# SCH_LED_drill_2025-12-10.net
KiCad netlist of a schematic drawn in EasyEDA
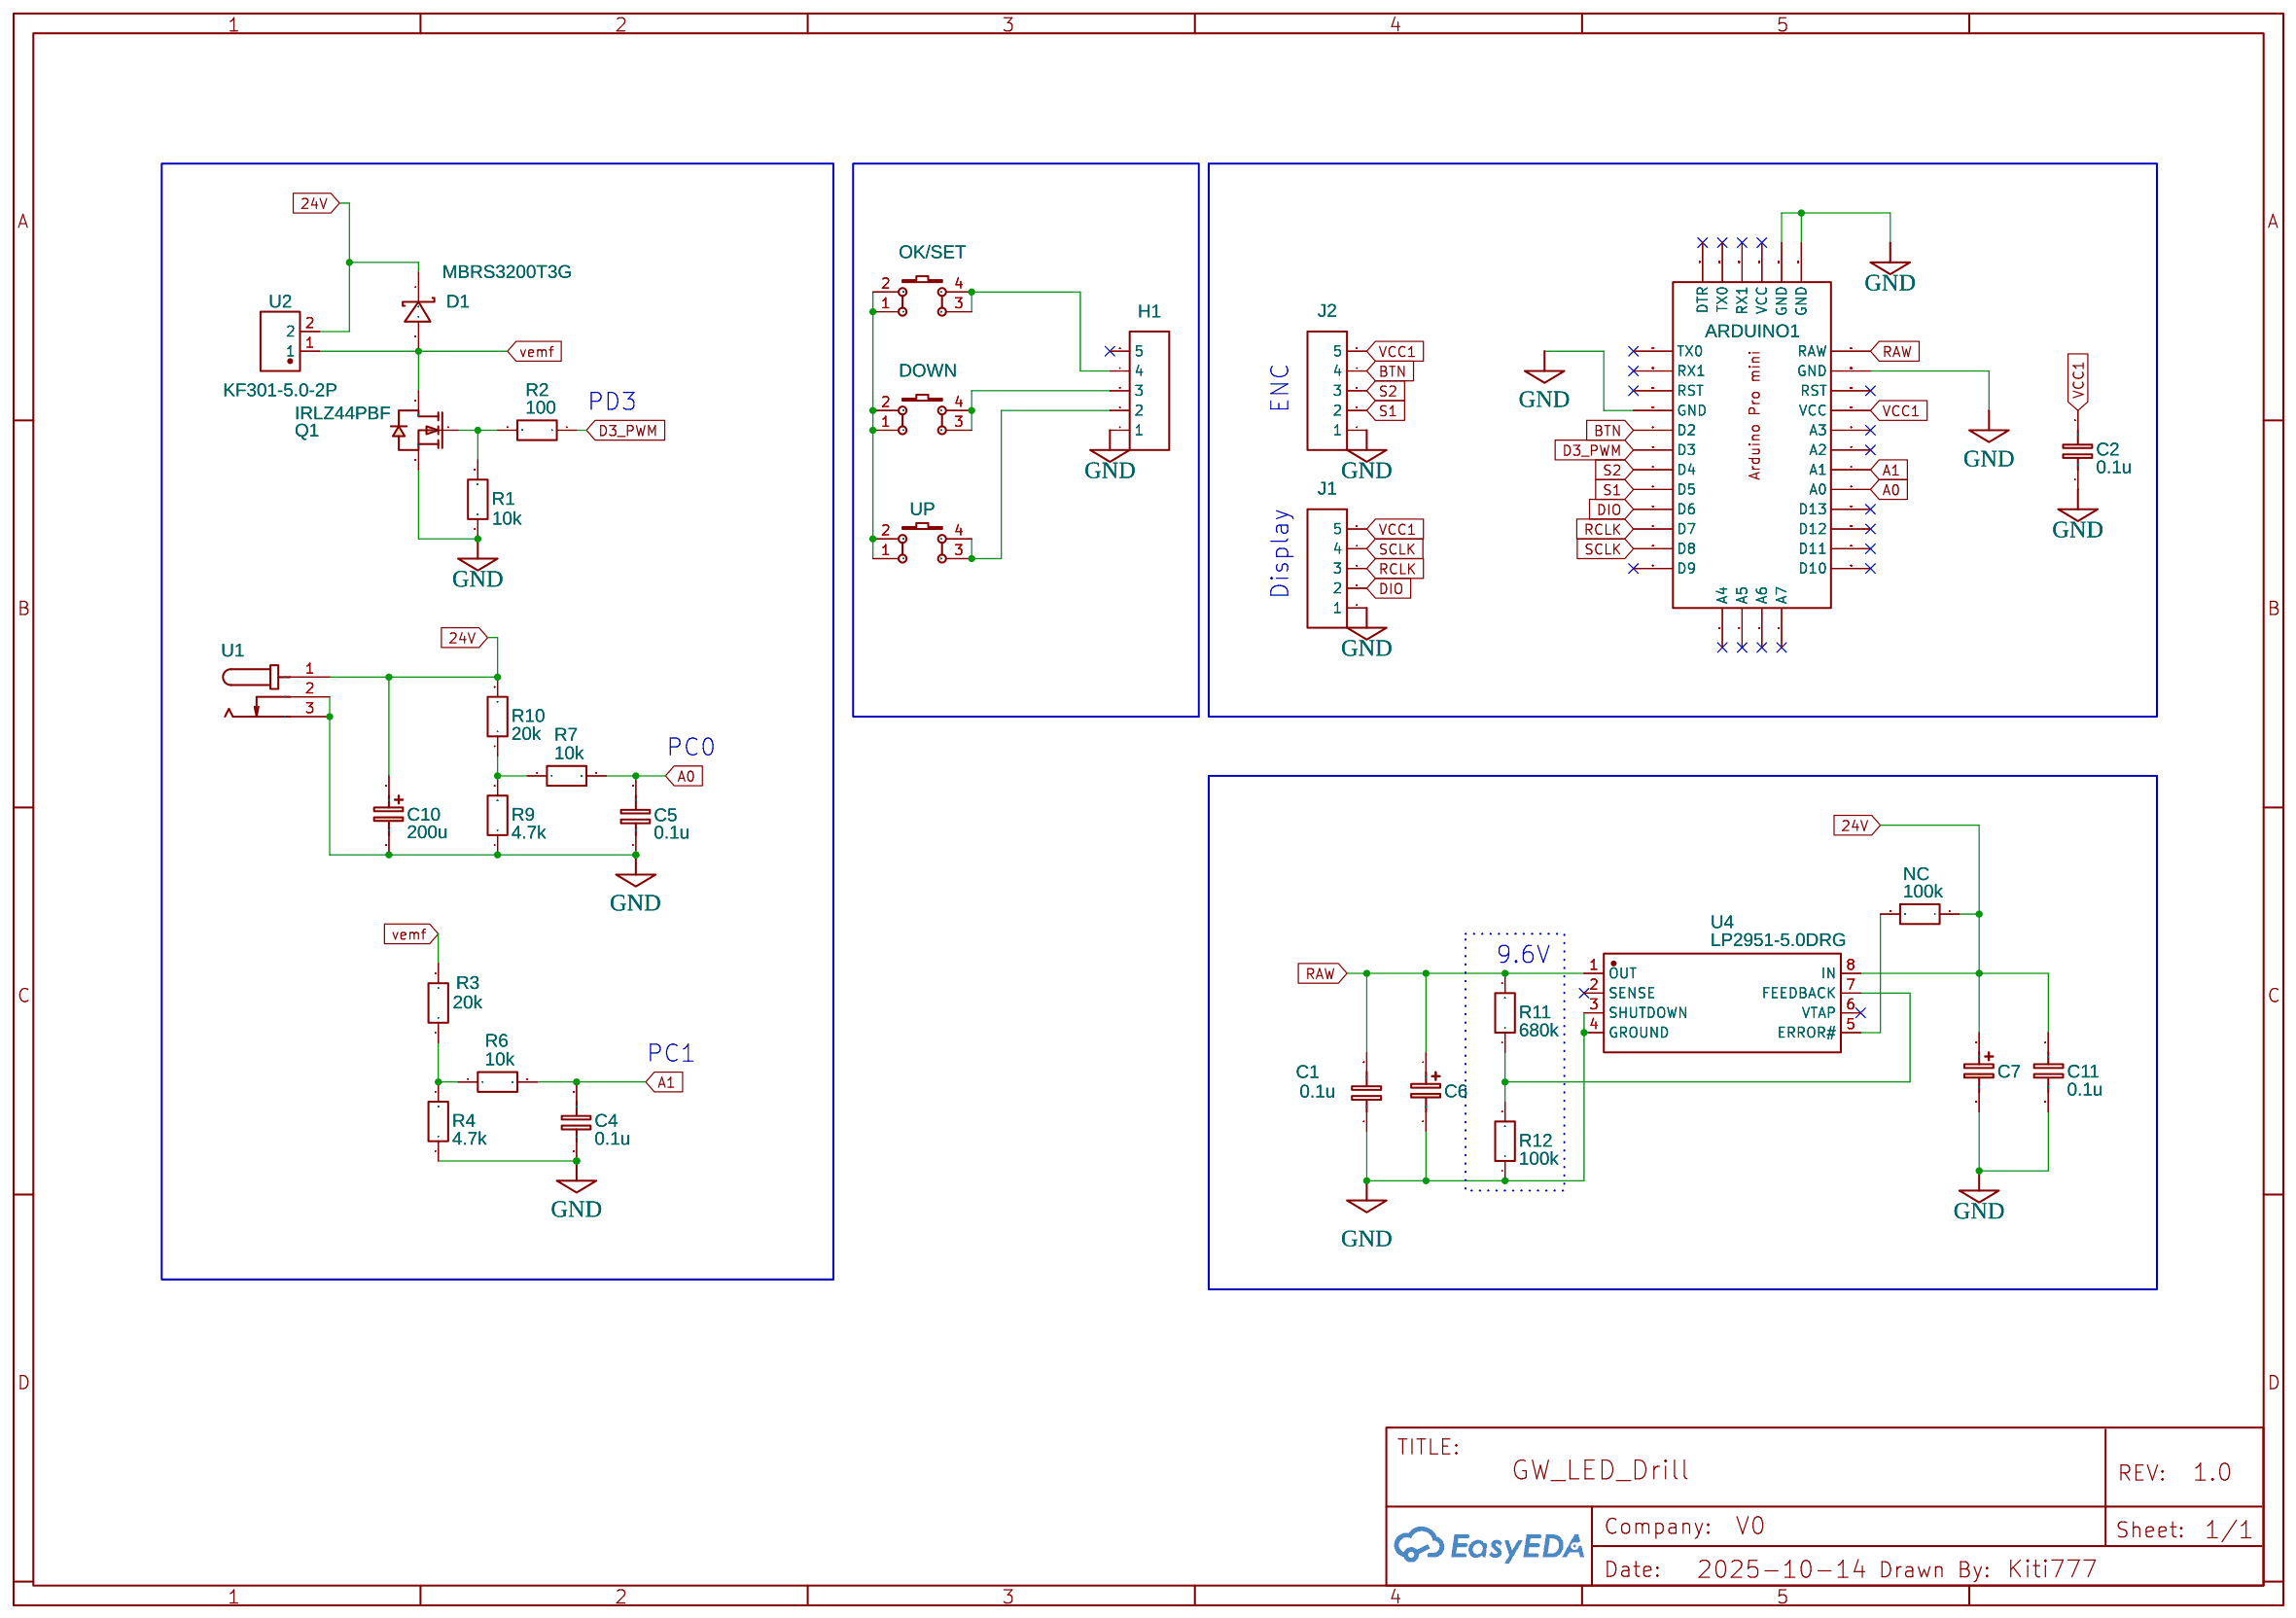
[diagram p0: schematic sheet]

(export (version "E")
  (design (tool "Eeschema 10.0.6"))
  (components
    (comp (ref "ARDUINO1") (value "ARDUINO PRO MINI") (libsource (lib "") (part "ARDUINO PRO MINI")))
    (comp (ref "C1") (value "0.1u") (libsource (lib "") (part "C_1206_EU_2")))
    (comp (ref "C2") (value "0.1u") (libsource (lib "") (part "C_0805_EU_1")))
    (comp (ref "C4") (value "0.1u") (libsource (lib "") (part "C_0805_EU")))
    (comp (ref "C5") (value "0.1u") (libsource (lib "") (part "C_1206_EU_1")))
    (comp (ref "C6")
      (value "TANTALUM SMT CAPACITOR 330UF C")
      (fields (field (name "Manufacturer Part") "Tantalum SMT Capacitor 330uF C"))
      (libsource (lib "") (part "TANTALUM SMT CAPACITOR 330UF C"))
    )
    (comp (ref "C7")
      (value "TANTALUM SMT CAPACITOR 330UF C")
      (fields (field (name "Manufacturer Part") "Tantalum SMT Capacitor 330uF C"))
      (libsource (lib "") (part "TANTALUM SMT CAPACITOR 330UF C"))
    )
    (comp (ref "C10") (value "200u") (libsource (lib "") (part "CE_SMD_D8.0×H10.5_EU")))
    (comp (ref "C11") (value "0.1u") (libsource (lib "") (part "C_1206_EU")))
    (comp (ref "D1")
      (value "MBRS3200T3G")
      (fields (field (name "Manufacturer") "onsemi(安森美)"))
      (libsource (lib "") (part "MBRS3200T3G"))
    )
    (comp (ref "DOWN")
      (value "K4-6×6_TH")
      (fields (field (name "Manufacturer Part") "K2-1102DP-E4SW-04") (field (name "Manufacturer") "韩国韩荣"))
      (libsource (lib "") (part "K4-6×6_TH"))
    )
    (comp (ref "H1") (value "HDR-F-2.54_1x5") (libsource (lib "") (part "HDR-F-2.54_1x5")))
    (comp (ref "J1") (value "HDR-M-2.54_1x5") (libsource (lib "") (part "HDR-M-2.54_1x5")))
    (comp (ref "J2") (value "HDR-M-2.54_1x5") (libsource (lib "") (part "HDR-M-2.54_1x5")))
    (comp (ref "NC") (value "100k") (libsource (lib "") (part "R_0805_EU_1")))
    (comp (ref "OK/SET")
      (value "K4-6×6_TH")
      (fields (field (name "Manufacturer Part") "K2-1102DP-E4SW-04") (field (name "Manufacturer") "韩国韩荣"))
      (libsource (lib "") (part "K4-6×6_TH_2"))
    )
    (comp (ref "Q1")
      (value "IRLZ44PBF")
      (fields (field (name "Manufacturer Part") "IRLZ44PBF-VB") (field (name "Manufacturer") "VBsemi(微碧半导体)"))
      (libsource (lib "") (part "IRLZ44PBF"))
    )
    (comp (ref "R1") (value "10k") (libsource (lib "") (part "R_1206_EU_1")))
    (comp (ref "R2") (value "100") (libsource (lib "") (part "R_1206_EU_2")))
    (comp (ref "R3") (value "20k") (libsource (lib "") (part "R_1206_EU_1")))
    (comp (ref "R4") (value "4.7k") (libsource (lib "") (part "R_1206_EU_1")))
    (comp (ref "R6") (value "10k") (libsource (lib "") (part "R_1206_EU")))
    (comp (ref "R7") (value "10k") (libsource (lib "") (part "R_1206_EU")))
    (comp (ref "R9") (value "4.7k") (libsource (lib "") (part "R_1206_EU_1")))
    (comp (ref "R10") (value "20k") (libsource (lib "") (part "R_1206_EU_1")))
    (comp (ref "R11") (value "680k") (libsource (lib "") (part "R_0805_EU")))
    (comp (ref "R12") (value "100k") (libsource (lib "") (part "R_0805_EU")))
    (comp (ref "U1")
      (value "ZX-DC-WC26.4")
      (fields (field (name "Manufacturer") "Megastar(兆星)"))
      (libsource (lib "") (part "ZX-DC-WC26.4"))
    )
    (comp (ref "U2")
      (value "KF301-5.0-2P")
      (fields (field (name "Manufacturer") "KEFA(科发)"))
      (libsource (lib "") (part "KF301-5.0-2P"))
    )
    (comp (ref "U4")
      (value "LP2951-5.0DRG")
      (fields (field (name "Manufacturer") "HGC(深圳汉芯)"))
      (libsource (lib "") (part "LP2951-5.0DRG"))
    )
    (comp (ref "UP")
      (value "K4-6×6_TH")
      (fields (field (name "Manufacturer Part") "K2-1102DP-E4SW-04") (field (name "Manufacturer") "韩国韩荣"))
      (libsource (lib "") (part "K4-6×6_TH_1"))
    )
  )
  (nets
    (net (code "1") (name "24V") (class "Default")
      (node (ref "C10") (pin "1") (pinfunction "1_1") (pintype "unspecified"))
      (node (ref "C11") (pin "1") (pinfunction "1_1") (pintype "unspecified"))
      (node (ref "C7") (pin "1") (pinfunction "1_1") (pintype "unspecified"))
      (node (ref "D1") (pin "1") (pinfunction "C_1") (pintype "unspecified"))
      (node (ref "NC") (pin "1") (pinfunction "1_1") (pintype "unspecified"))
      (node (ref "R10") (pin "2") (pinfunction "2_2") (pintype "unspecified"))
      (node (ref "U1") (pin "1") (pinfunction "1_1") (pintype "unspecified"))
      (node (ref "U2") (pin "2") (pinfunction "2_2") (pintype "unspecified"))
      (node (ref "U4") (pin "8") (pinfunction "IN_8") (pintype "unspecified"))
    )
    (net (code "2") (name "A0") (class "Default")
      (node (ref "ARDUINO1") (pin "A0") (pinfunction "A0_A0") (pintype "bidirectional"))
      (node (ref "C5") (pin "2") (pinfunction "2_2") (pintype "unspecified"))
      (node (ref "R7") (pin "2") (pinfunction "2_2") (pintype "unspecified"))
    )
    (net (code "3") (name "A1") (class "Default")
      (node (ref "ARDUINO1") (pin "A1") (pinfunction "A1_A1") (pintype "bidirectional"))
      (node (ref "C4") (pin "2") (pinfunction "2_2") (pintype "unspecified"))
      (node (ref "R6") (pin "2") (pinfunction "2_2") (pintype "unspecified"))
    )
    (net (code "4") (name "BTN") (class "Default")
      (node (ref "ARDUINO1") (pin "D2") (pinfunction "D2_D2") (pintype "bidirectional"))
      (node (ref "J2") (pin "4") (pinfunction "4_4") (pintype "unspecified"))
    )
    (net (code "5") (name "D3_PWM") (class "Default")
      (node (ref "ARDUINO1") (pin "D3") (pinfunction "D3_D3") (pintype "bidirectional"))
      (node (ref "R2") (pin "1") (pinfunction "1_1") (pintype "unspecified"))
    )
    (net (code "6") (name "DIO") (class "Default")
      (node (ref "ARDUINO1") (pin "D6") (pinfunction "D6_D6") (pintype "bidirectional"))
      (node (ref "J1") (pin "2") (pinfunction "2_2") (pintype "unspecified"))
    )
    (net (code "7") (name "GND") (class "Default")
      (node (ref "ARDUINO1") (pin "GND@0") (pinfunction "GND_GND@0") (pintype "bidirectional"))
      (node (ref "ARDUINO1") (pin "GND@1") (pinfunction "GND_GND@1") (pintype "bidirectional"))
      (node (ref "ARDUINO1") (pin "GND@2") (pinfunction "GND_GND@2") (pintype "bidirectional"))
      (node (ref "ARDUINO1") (pin "GND@3") (pinfunction "GND_GND@3") (pintype "bidirectional"))
      (node (ref "C1") (pin "1") (pinfunction "1_1") (pintype "unspecified"))
      (node (ref "C10") (pin "2") (pinfunction "2_2") (pintype "unspecified"))
      (node (ref "C11") (pin "2") (pinfunction "2_2") (pintype "unspecified"))
      (node (ref "C2") (pin "1") (pinfunction "1_1") (pintype "unspecified"))
      (node (ref "C4") (pin "1") (pinfunction "1_1") (pintype "unspecified"))
      (node (ref "C5") (pin "1") (pinfunction "1_1") (pintype "unspecified"))
      (node (ref "C6") (pin "2") (pinfunction "2_2") (pintype "unspecified"))
      (node (ref "C7") (pin "2") (pinfunction "2_2") (pintype "unspecified"))
      (node (ref "H1") (pin "1") (pinfunction "1_1") (pintype "unspecified"))
      (node (ref "J1") (pin "1") (pinfunction "1_1") (pintype "unspecified"))
      (node (ref "J2") (pin "1") (pinfunction "1_1") (pintype "unspecified"))
      (node (ref "Q1") (pin "3") (pinfunction "S_3") (pintype "unspecified"))
      (node (ref "R1") (pin "1") (pinfunction "1_1") (pintype "unspecified"))
      (node (ref "R12") (pin "1") (pinfunction "1_1") (pintype "unspecified"))
      (node (ref "R4") (pin "1") (pinfunction "1_1") (pintype "unspecified"))
      (node (ref "R9") (pin "1") (pinfunction "1_1") (pintype "unspecified"))
      (node (ref "U1") (pin "2") (pinfunction "2_2") (pintype "unspecified"))
      (node (ref "U1") (pin "3") (pinfunction "3_3") (pintype "unspecified"))
      (node (ref "U4") (pin "3") (pinfunction "SHUTDOWN_3") (pintype "unspecified"))
      (node (ref "U4") (pin "4") (pinfunction "GROUND_4") (pintype "unspecified"))
    )
    (net (code "8") (name "Net-(DOWN-Pad1)") (class "Default")
      (node (ref "DOWN") (pin "1") (pinfunction "1_1") (pintype "unspecified"))
      (node (ref "DOWN") (pin "2") (pinfunction "2_2") (pintype "unspecified"))
      (node (ref "OK/SET") (pin "1") (pinfunction "1_1") (pintype "unspecified"))
      (node (ref "OK/SET") (pin "2") (pinfunction "2_2") (pintype "unspecified"))
      (node (ref "UP") (pin "1") (pinfunction "1_1") (pintype "unspecified"))
      (node (ref "UP") (pin "2") (pinfunction "2_2") (pintype "unspecified"))
    )
    (net (code "9") (name "Net-(DOWN-Pad3)") (class "Default")
      (node (ref "DOWN") (pin "3") (pinfunction "3_3") (pintype "unspecified"))
      (node (ref "DOWN") (pin "4") (pinfunction "4_4") (pintype "unspecified"))
      (node (ref "H1") (pin "3") (pinfunction "3_3") (pintype "unspecified"))
    )
    (net (code "10") (name "Net-(H1-Pad2)") (class "Default")
      (node (ref "H1") (pin "2") (pinfunction "2_2") (pintype "unspecified"))
      (node (ref "UP") (pin "3") (pinfunction "3_3") (pintype "unspecified"))
      (node (ref "UP") (pin "4") (pinfunction "4_4") (pintype "unspecified"))
    )
    (net (code "11") (name "Net-(H1-Pad4)") (class "Default")
      (node (ref "H1") (pin "4") (pinfunction "4_4") (pintype "unspecified"))
      (node (ref "OK/SET") (pin "3") (pinfunction "3_3") (pintype "unspecified"))
      (node (ref "OK/SET") (pin "4") (pinfunction "4_4") (pintype "unspecified"))
    )
    (net (code "12") (name "Net-(Q1-G)") (class "Default")
      (node (ref "Q1") (pin "1") (pinfunction "G_1") (pintype "unspecified"))
      (node (ref "R1") (pin "2") (pinfunction "2_2") (pintype "unspecified"))
      (node (ref "R2") (pin "2") (pinfunction "2_2") (pintype "unspecified"))
    )
    (net (code "13") (name "Net-(R3-Pad1)") (class "Default")
      (node (ref "R3") (pin "1") (pinfunction "1_1") (pintype "unspecified"))
      (node (ref "R4") (pin "2") (pinfunction "2_2") (pintype "unspecified"))
      (node (ref "R6") (pin "1") (pinfunction "1_1") (pintype "unspecified"))
    )
    (net (code "14") (name "Net-(R10-Pad1)") (class "Default")
      (node (ref "R10") (pin "1") (pinfunction "1_1") (pintype "unspecified"))
      (node (ref "R7") (pin "1") (pinfunction "1_1") (pintype "unspecified"))
      (node (ref "R9") (pin "2") (pinfunction "2_2") (pintype "unspecified"))
    )
    (net (code "15") (name "Net-(U4-ERROR#)") (class "Default")
      (node (ref "NC") (pin "2") (pinfunction "2_2") (pintype "unspecified"))
      (node (ref "U4") (pin "5") (pinfunction "ERROR#_5") (pintype "unspecified"))
    )
    (net (code "16") (name "Net-(U4-FEEDBACK)") (class "Default")
      (node (ref "R11") (pin "1") (pinfunction "1_1") (pintype "unspecified"))
      (node (ref "R12") (pin "2") (pinfunction "2_2") (pintype "unspecified"))
      (node (ref "U4") (pin "7") (pinfunction "FEEDBACK_7") (pintype "unspecified"))
    )
    (net (code "17") (name "RAW") (class "Default")
      (node (ref "ARDUINO1") (pin "RAW") (pinfunction "RAW_RAW") (pintype "bidirectional"))
      (node (ref "C1") (pin "2") (pinfunction "2_2") (pintype "unspecified"))
      (node (ref "C6") (pin "1") (pinfunction "1_1") (pintype "unspecified"))
      (node (ref "R11") (pin "2") (pinfunction "2_2") (pintype "unspecified"))
      (node (ref "U4") (pin "1") (pinfunction "OUT_1") (pintype "unspecified"))
    )
    (net (code "18") (name "RCLK") (class "Default")
      (node (ref "ARDUINO1") (pin "D7") (pinfunction "D7_D7") (pintype "bidirectional"))
      (node (ref "J1") (pin "3") (pinfunction "3_3") (pintype "unspecified"))
    )
    (net (code "19") (name "S1") (class "Default")
      (node (ref "ARDUINO1") (pin "D5") (pinfunction "D5_D5") (pintype "bidirectional"))
      (node (ref "J2") (pin "2") (pinfunction "2_2") (pintype "unspecified"))
    )
    (net (code "20") (name "S2") (class "Default")
      (node (ref "ARDUINO1") (pin "D4") (pinfunction "D4_D4") (pintype "bidirectional"))
      (node (ref "J2") (pin "3") (pinfunction "3_3") (pintype "unspecified"))
    )
    (net (code "21") (name "SCLK") (class "Default")
      (node (ref "ARDUINO1") (pin "D8") (pinfunction "D8_D8") (pintype "bidirectional"))
      (node (ref "J1") (pin "4") (pinfunction "4_4") (pintype "unspecified"))
    )
    (net (code "22") (name "VCC1") (class "Default")
      (node (ref "ARDUINO1") (pin "VCC@1") (pinfunction "VCC_VCC@1") (pintype "bidirectional"))
      (node (ref "C2") (pin "2") (pinfunction "2_2") (pintype "unspecified"))
      (node (ref "J1") (pin "5") (pinfunction "5_5") (pintype "unspecified"))
      (node (ref "J2") (pin "5") (pinfunction "5_5") (pintype "unspecified"))
    )
    (net (code "23") (name "unconnected-(ARDUINO1-PadA2)") (class "Default")
      (node (ref "ARDUINO1") (pin "A2") (pinfunction "A2_A2") (pintype "bidirectional+no_connect"))
    )
    (net (code "24") (name "unconnected-(ARDUINO1-PadA3)") (class "Default")
      (node (ref "ARDUINO1") (pin "A3") (pinfunction "A3_A3") (pintype "bidirectional+no_connect"))
    )
    (net (code "25") (name "unconnected-(ARDUINO1-PadA4)") (class "Default")
      (node (ref "ARDUINO1") (pin "A4") (pinfunction "A4_A4") (pintype "bidirectional+no_connect"))
    )
    (net (code "26") (name "unconnected-(ARDUINO1-PadA5)") (class "Default")
      (node (ref "ARDUINO1") (pin "A5") (pinfunction "A5_A5") (pintype "bidirectional+no_connect"))
    )
    (net (code "27") (name "unconnected-(ARDUINO1-PadA6)") (class "Default")
      (node (ref "ARDUINO1") (pin "A6") (pinfunction "A6_A6") (pintype "bidirectional+no_connect"))
    )
    (net (code "28") (name "unconnected-(ARDUINO1-PadA7)") (class "Default")
      (node (ref "ARDUINO1") (pin "A7") (pinfunction "A7_A7") (pintype "bidirectional+no_connect"))
    )
    (net (code "29") (name "unconnected-(ARDUINO1-PadD9)") (class "Default")
      (node (ref "ARDUINO1") (pin "D9") (pinfunction "D9_D9") (pintype "bidirectional+no_connect"))
    )
    (net (code "30") (name "unconnected-(ARDUINO1-PadD10)") (class "Default")
      (node (ref "ARDUINO1") (pin "D10") (pinfunction "D10_D10") (pintype "bidirectional+no_connect"))
    )
    (net (code "31") (name "unconnected-(ARDUINO1-PadD11)") (class "Default")
      (node (ref "ARDUINO1") (pin "D11") (pinfunction "D11_D11") (pintype "bidirectional+no_connect"))
    )
    (net (code "32") (name "unconnected-(ARDUINO1-PadD12)") (class "Default")
      (node (ref "ARDUINO1") (pin "D12") (pinfunction "D12_D12") (pintype "bidirectional+no_connect"))
    )
    (net (code "33") (name "unconnected-(ARDUINO1-PadD13)") (class "Default")
      (node (ref "ARDUINO1") (pin "D13") (pinfunction "D13_D13") (pintype "bidirectional+no_connect"))
    )
    (net (code "34") (name "unconnected-(ARDUINO1-PadDTR)") (class "Default")
      (node (ref "ARDUINO1") (pin "DTR") (pinfunction "DTR_DTR") (pintype "bidirectional+no_connect"))
    )
    (net (code "35") (name "unconnected-(ARDUINO1-RST-PadRST@0)") (class "Default")
      (node (ref "ARDUINO1") (pin "RST@0") (pinfunction "RST_RST@0") (pintype "bidirectional+no_connect"))
    )
    (net (code "36") (name "unconnected-(ARDUINO1-RST-PadRST@1)") (class "Default")
      (node (ref "ARDUINO1") (pin "RST@1") (pinfunction "RST_RST@1") (pintype "bidirectional+no_connect"))
    )
    (net (code "37") (name "unconnected-(ARDUINO1-RX1-PadRX1@0)") (class "Default")
      (node (ref "ARDUINO1") (pin "RX1@0") (pinfunction "RX1_RX1@0") (pintype "bidirectional+no_connect"))
    )
    (net (code "38") (name "unconnected-(ARDUINO1-RX1-PadRX1@1)") (class "Default")
      (node (ref "ARDUINO1") (pin "RX1@1") (pinfunction "RX1_RX1@1") (pintype "bidirectional+no_connect"))
    )
    (net (code "39") (name "unconnected-(ARDUINO1-TX0-PadTX0@0)") (class "Default")
      (node (ref "ARDUINO1") (pin "TX0@0") (pinfunction "TX0_TX0@0") (pintype "bidirectional+no_connect"))
    )
    (net (code "40") (name "unconnected-(ARDUINO1-TX0-PadTX0@1)") (class "Default")
      (node (ref "ARDUINO1") (pin "TX0@1") (pinfunction "TX0_TX0@1") (pintype "bidirectional+no_connect"))
    )
    (net (code "41") (name "unconnected-(ARDUINO1-VCC-PadVCC@0)") (class "Default")
      (node (ref "ARDUINO1") (pin "VCC@0") (pinfunction "VCC_VCC@0") (pintype "bidirectional+no_connect"))
    )
    (net (code "42") (name "unconnected-(H1-Pad5)") (class "Default")
      (node (ref "H1") (pin "5") (pinfunction "5_5") (pintype "unspecified+no_connect"))
    )
    (net (code "43") (name "unconnected-(U4-SENSE-Pad2)") (class "Default")
      (node (ref "U4") (pin "2") (pinfunction "SENSE_2") (pintype "unspecified+no_connect"))
    )
    (net (code "44") (name "unconnected-(U4-VTAP-Pad6)") (class "Default")
      (node (ref "U4") (pin "6") (pinfunction "VTAP_6") (pintype "unspecified+no_connect"))
    )
    (net (code "45") (name "vemf") (class "Default")
      (node (ref "D1") (pin "2") (pinfunction "A_2") (pintype "unspecified"))
      (node (ref "Q1") (pin "2") (pinfunction "D_2") (pintype "unspecified"))
      (node (ref "R3") (pin "2") (pinfunction "2_2") (pintype "unspecified"))
      (node (ref "U2") (pin "1") (pinfunction "1_1") (pintype "unspecified"))
    )
  )
)
